# half-pint-turbidimeter_tsl230rd_tsl267_2.net
KiCad netlist of a schematic drawn in EAGLE
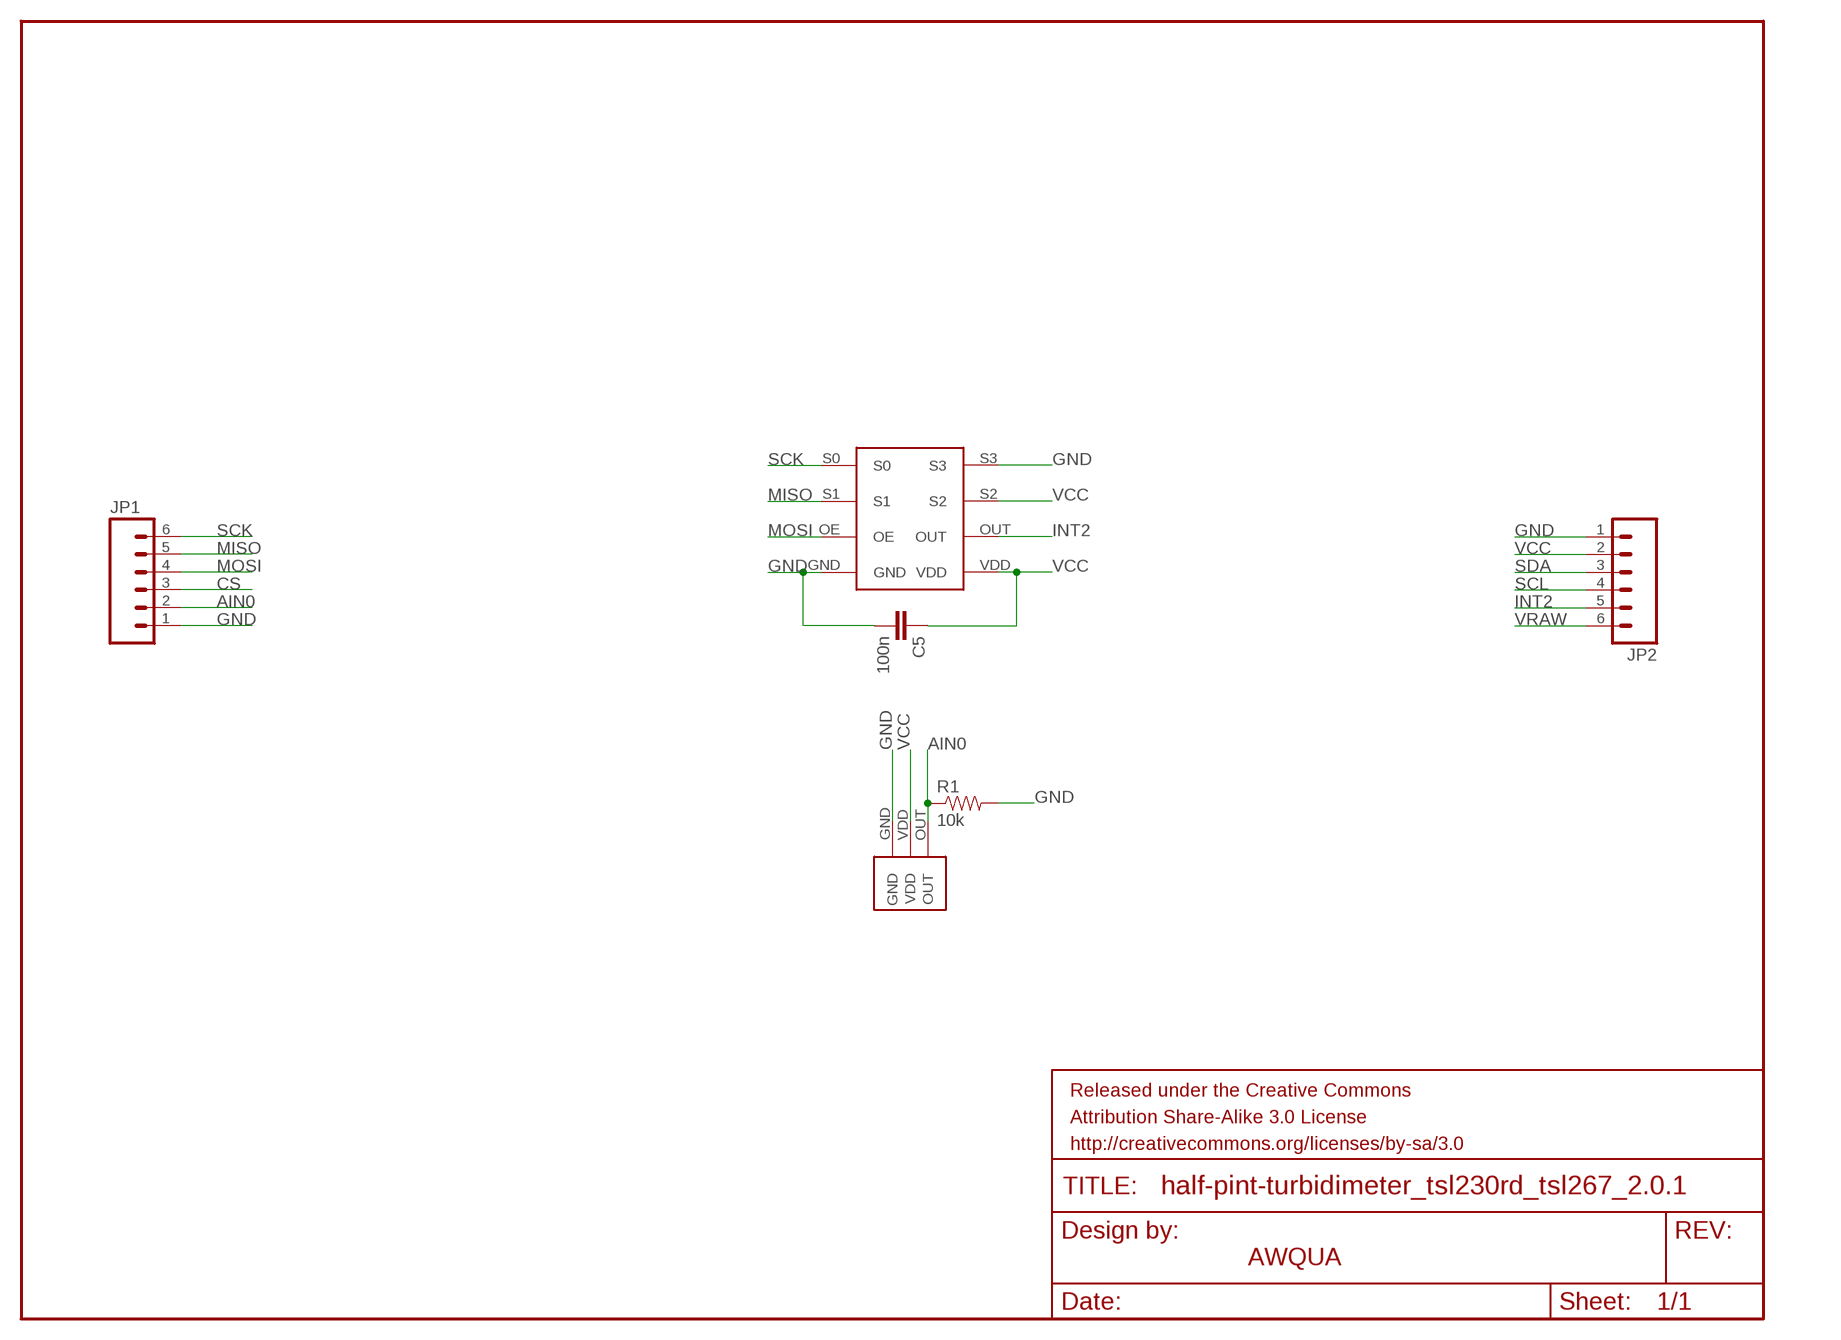
[diagram p0: schematic, sheet 1]

(export (version "E")
  (design (tool "Eeschema 10.0.6"))
  (components
    (comp (ref "C5")
      (value "100n")
      (footprint "eagle-import:0603-CAP")
      (libsource (lib "eagle-import") (part "CAP0603-CAP"))
    )
    (comp (ref "FRAME1")
      (value "FRAME-LETTER")
      (footprint "eagle-import:CREATIVE_COMMONS")
      (libsource (lib "eagle-import") (part "FRAME-LETTER"))
    )
    (comp (ref "JP1")
      (value "M06SIP")
      (footprint "eagle-import:1X06")
      (libsource (lib "eagle-import") (part "M06SIP"))
    )
    (comp (ref "JP2")
      (value "M06SIP")
      (footprint "eagle-import:1X06")
      (libsource (lib "eagle-import") (part "M06SIP"))
    )
    (comp (ref "R1")
      (value "10k")
      (footprint "eagle-import:0603-RES")
      (libsource (lib "eagle-import") (part "RESISTOR0603-RES"))
    )
    (comp (ref "U$1")
      (value "TSL267")
      (footprint "eagle-import:TSL267")
      (libsource (lib "eagle-import") (part "TSL267"))
    )
    (comp (ref "U$6")
      (value "TSL230RDSMD")
      (footprint "eagle-import:TSL230RD")
      (libsource (lib "eagle-import") (part "TSL230RDSMD"))
    )
  )
  (nets
    (net (code "1") (name "/AIN0") (class "Default")
      (node (ref "JP1") (pin "2") (pinfunction "2_2") (pintype "passive"))
      (node (ref "R1") (pin "1") (pinfunction "1_1") (pintype "passive"))
      (node (ref "U$1") (pin "OUT") (pinfunction "OUT_OUT") (pintype "bidirectional"))
    )
    (net (code "2") (name "/CS") (class "Default")
      (node (ref "JP1") (pin "3") (pinfunction "3_3") (pintype "passive"))
    )
    (net (code "3") (name "/GND") (class "Default")
      (node (ref "C5") (pin "2") (pinfunction "2_2") (pintype "passive"))
      (node (ref "JP1") (pin "1") (pinfunction "1_1") (pintype "passive"))
      (node (ref "JP2") (pin "1") (pinfunction "1_1") (pintype "passive"))
      (node (ref "R1") (pin "2") (pinfunction "2_2") (pintype "passive"))
      (node (ref "U$1") (pin "GND") (pinfunction "GND_GND") (pintype "bidirectional"))
      (node (ref "U$6") (pin "GND") (pinfunction "GND_GND") (pintype "bidirectional"))
      (node (ref "U$6") (pin "S3") (pinfunction "S3_S3") (pintype "bidirectional"))
    )
    (net (code "4") (name "/INT2") (class "Default")
      (node (ref "JP2") (pin "5") (pinfunction "5_5") (pintype "passive"))
      (node (ref "U$6") (pin "OUT") (pinfunction "OUT_OUT") (pintype "bidirectional"))
    )
    (net (code "5") (name "/MISO") (class "Default")
      (node (ref "JP1") (pin "5") (pinfunction "5_5") (pintype "passive"))
      (node (ref "U$6") (pin "S1") (pinfunction "S1_S1") (pintype "bidirectional"))
    )
    (net (code "6") (name "/MOSI") (class "Default")
      (node (ref "JP1") (pin "4") (pinfunction "4_4") (pintype "passive"))
      (node (ref "U$6") (pin "OE") (pinfunction "OE_OE") (pintype "bidirectional"))
    )
    (net (code "7") (name "/SCK") (class "Default")
      (node (ref "JP1") (pin "6") (pinfunction "6_6") (pintype "passive"))
      (node (ref "U$6") (pin "S0") (pinfunction "S0_S0") (pintype "bidirectional"))
    )
    (net (code "8") (name "/SCL") (class "Default")
      (node (ref "JP2") (pin "4") (pinfunction "4_4") (pintype "passive"))
    )
    (net (code "9") (name "/SDA") (class "Default")
      (node (ref "JP2") (pin "3") (pinfunction "3_3") (pintype "passive"))
    )
    (net (code "10") (name "/VCC") (class "Default")
      (node (ref "C5") (pin "1") (pinfunction "1_1") (pintype "passive"))
      (node (ref "JP2") (pin "2") (pinfunction "2_2") (pintype "passive"))
      (node (ref "U$1") (pin "VDD") (pinfunction "VDD_VDD") (pintype "bidirectional"))
      (node (ref "U$6") (pin "S2") (pinfunction "S2_S2") (pintype "bidirectional"))
      (node (ref "U$6") (pin "VDD") (pinfunction "VDD_VDD") (pintype "bidirectional"))
    )
    (net (code "11") (name "/VRAW") (class "Default")
      (node (ref "JP2") (pin "6") (pinfunction "6_6") (pintype "passive"))
    )
  )
)
